# AlteraUSBBlaster2TC.net
KiCad netlist of a schematic drawn in EAGLE
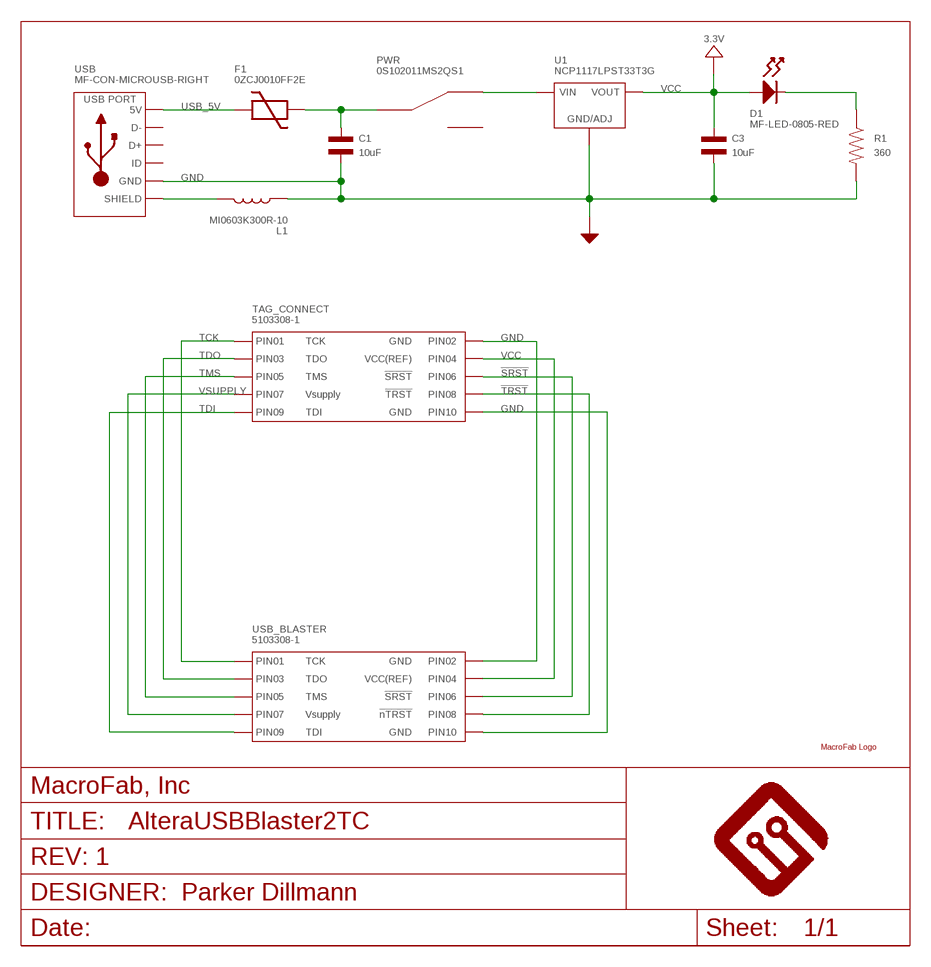
[diagram p0: schematic, sheet 1]

(export (version "E")
  (design (tool "Eeschema 10.0.6"))
  (components
    (comp (ref "C1")
      (value "10uF")
      (footprint "eagle-import:C1206")
      (fields (field (name "MPN") "MF-CAP-1206-10uF"))
      (libsource (lib "eagle-import") (part "CAPACITOR_NP_1206"))
    )
    (comp (ref "C3")
      (value "10uF")
      (footprint "eagle-import:C1206")
      (fields (field (name "MPN") "MF-CAP-1206-10uF"))
      (libsource (lib "eagle-import") (part "CAPACITOR_NP_1206"))
    )
    (comp (ref "D1")
      (value "MF-LED-0805-RED")
      (footprint "eagle-import:LED0805")
      (fields (field (name "HOUSEPART") "YES"))
      (libsource (lib "eagle-import") (part "LED_SINGLE-0805-RED"))
    )
    (comp (ref "F1")
      (value "0ZCJ0010FF2E")
      (footprint "eagle-import:1206")
      (libsource (lib "eagle-import") (part "PTC_FUSE_1206"))
    )
    (comp (ref "FRAME1")
      (value "MF_FRAMEDEFAULT")
      (footprint "eagle-import:MF_FRAME_DEFAULT")
      (fields
        (field (name "HOUSEPART") "0")
        (field (name "DNAME") "Parker Dillmann")
        (field (name "REVNUM") "REV: 1")
      )
      (libsource (lib "eagle-import") (part "MF_FRAMEDEFAULT"))
    )
    (comp (ref "L1")
      (value "MI0603K300R-10")
      (footprint "eagle-import:L0603")
      (fields (field (name "MPN") "MI0603K300R-10"))
      (libsource (lib "eagle-import") (part "INDUCTOR_0603"))
    )
    (comp (ref "PWR")
      (value "0S102011MS2QS1")
      (footprint "eagle-import:0S102011MS2QS1")
      (libsource (lib "eagle-import") (part "SPDT_0S102011MS2QS1"))
    )
    (comp (ref "R1")
      (value "360")
      (footprint "eagle-import:R0805")
      (fields (field (name "MPN") "MF-RES-0805-360"))
      (libsource (lib "eagle-import") (part "RESISTOR_0805"))
    )
    (comp (ref "TAG_CONNECT")
      (value "5103308-1")
      (footprint "eagle-import:5103308-1")
      (fields
        (field (name "LABEL01") "TCK")
        (field (name "LABEL02") "GND")
        (field (name "LABEL03") "TDO")
        (field (name "LABEL04") "VCC(REF)")
        (field (name "LABEL05") "TMS")
        (field (name "LABEL06") "!SRST")
        (field (name "LABEL07") "Vsupply")
        (field (name "LABEL08") "!TRST")
        (field (name "LABEL09") "TDI")
        (field (name "LABEL10") "GND")
        (field (name "MPN") "5103308-1")
        (field (name "POPULATE") "1")
      )
      (libsource (lib "eagle-import") (part "CON_02X05_5103308-1"))
    )
    (comp (ref "U$3")
      (value "MF_LOGOLOGO_MEDIUM")
      (footprint "eagle-import:MF_LOGO_MEDIUM")
      (libsource (lib "eagle-import") (part "MF_LOGOLOGO_MEDIUM"))
    )
    (comp (ref "U1")
      (value "NCP1117LPST33T3G")
      (footprint "eagle-import:SOT-223-3")
      (fields (field (name "HOUSEPART") "NO"))
      (libsource (lib "eagle-import") (part "NCP1117LPST33T3G"))
    )
    (comp (ref "USB")
      (value "MF-CON-MICROUSB-RIGHT")
      (footprint "eagle-import:MICROUSB-RIGHT")
      (fields (field (name "HOUSEPART") "YES"))
      (libsource (lib "eagle-import") (part "USB_MICRO_RIGHT"))
    )
    (comp (ref "USB_BLASTER")
      (value "5103308-1")
      (footprint "eagle-import:5103308-1")
      (fields
        (field (name "LABEL01") "TCK")
        (field (name "LABEL02") "GND")
        (field (name "LABEL03") "TDO")
        (field (name "LABEL04") "VCC(REF)")
        (field (name "LABEL05") "TMS")
        (field (name "LABEL06") "!SRST")
        (field (name "LABEL07") "Vsupply")
        (field (name "LABEL08") "!nTRST")
        (field (name "LABEL09") "TDI")
        (field (name "LABEL10") "GND")
        (field (name "MPN") "5103308-1")
        (field (name "POPULATE") "1")
      )
      (libsource (lib "eagle-import") (part "CON_02X05_5103308-1"))
    )
  )
  (nets
    (net (code "1") (name "/TCK") (class "Default")
      (node (ref "TAG_CONNECT") (pin "1") (pinfunction "PIN1_1") (pintype "bidirectional"))
      (node (ref "USB_BLASTER") (pin "1") (pinfunction "PIN1_1") (pintype "bidirectional"))
    )
    (net (code "2") (name "/TDI") (class "Default")
      (node (ref "TAG_CONNECT") (pin "9") (pinfunction "PIN9_9") (pintype "bidirectional"))
      (node (ref "USB_BLASTER") (pin "9") (pinfunction "PIN9_9") (pintype "bidirectional"))
    )
    (net (code "3") (name "/TDO") (class "Default")
      (node (ref "TAG_CONNECT") (pin "3") (pinfunction "PIN3_3") (pintype "bidirectional"))
      (node (ref "USB_BLASTER") (pin "3") (pinfunction "PIN3_3") (pintype "bidirectional"))
    )
    (net (code "4") (name "/TMS") (class "Default")
      (node (ref "TAG_CONNECT") (pin "5") (pinfunction "PIN5_5") (pintype "bidirectional"))
      (node (ref "USB_BLASTER") (pin "5") (pinfunction "PIN5_5") (pintype "bidirectional"))
    )
    (net (code "5") (name "/USB_5V") (class "Default")
      (node (ref "F1") (pin "1") (pinfunction "P$1_1") (pintype "bidirectional"))
      (node (ref "USB") (pin "1") (pinfunction "5V_1") (pintype "power_in"))
    )
    (net (code "6") (name "/VSUPPLY") (class "Default")
      (node (ref "TAG_CONNECT") (pin "7") (pinfunction "PIN7_7") (pintype "bidirectional"))
      (node (ref "USB_BLASTER") (pin "7") (pinfunction "PIN7_7") (pintype "bidirectional"))
    )
    (net (code "7") (name "/~{SRST}") (class "Default")
      (node (ref "TAG_CONNECT") (pin "6") (pinfunction "PIN6_6") (pintype "bidirectional"))
      (node (ref "USB_BLASTER") (pin "6") (pinfunction "PIN6_6") (pintype "bidirectional"))
    )
    (net (code "8") (name "/~{TRST}") (class "Default")
      (node (ref "TAG_CONNECT") (pin "8") (pinfunction "PIN8_8") (pintype "bidirectional"))
      (node (ref "USB_BLASTER") (pin "8") (pinfunction "PIN8_8") (pintype "bidirectional"))
    )
    (net (code "9") (name "3.3V") (class "Default")
      (node (ref "C3") (pin "P$1") (pinfunction "P$1_P$1") (pintype "passive"))
      (node (ref "D1") (pin "ANODE") (pinfunction "ANODE_ANODE") (pintype "power_in"))
      (node (ref "TAG_CONNECT") (pin "4") (pinfunction "PIN4_4") (pintype "bidirectional"))
      (node (ref "U1") (pin "P$1") (pinfunction "VOUT_P$1") (pintype "bidirectional"))
      (node (ref "U1") (pin "P$3") (pinfunction "VOUT_P$3") (pintype "bidirectional"))
      (node (ref "USB_BLASTER") (pin "4") (pinfunction "PIN4_4") (pintype "bidirectional"))
    )
    (net (code "10") (name "GND_RAIL") (class "Default")
      (node (ref "C1") (pin "P$2") (pinfunction "P$2_P$2") (pintype "passive"))
      (node (ref "C3") (pin "P$2") (pinfunction "P$2_P$2") (pintype "passive"))
      (node (ref "L1") (pin "P$1") (pinfunction "P$1_P$1") (pintype "passive"))
      (node (ref "R1") (pin "P$2") (pinfunction "P$2_P$2") (pintype "passive"))
      (node (ref "TAG_CONNECT") (pin "10") (pinfunction "PIN10_10") (pintype "bidirectional"))
      (node (ref "TAG_CONNECT") (pin "2") (pinfunction "PIN2_2") (pintype "bidirectional"))
      (node (ref "U1") (pin "P$2") (pinfunction "GND/ADJ_P$2") (pintype "bidirectional"))
      (node (ref "USB") (pin "5") (pinfunction "GND_5") (pintype "power_in"))
      (node (ref "USB_BLASTER") (pin "10") (pinfunction "PIN10_10") (pintype "bidirectional"))
      (node (ref "USB_BLASTER") (pin "2") (pinfunction "PIN2_2") (pintype "bidirectional"))
    )
    (net (code "11") (name "Net-(D1-PadCATHODE)") (class "Default")
      (node (ref "D1") (pin "CATHODE") (pinfunction "CATHODE_CATHODE") (pintype "power_in"))
      (node (ref "R1") (pin "P$1") (pinfunction "P$1_P$1") (pintype "passive"))
    )
    (net (code "12") (name "Net-(F1-P$2)") (class "Default")
      (node (ref "C1") (pin "P$1") (pinfunction "P$1_P$1") (pintype "passive"))
      (node (ref "F1") (pin "2") (pinfunction "P$2_2") (pintype "bidirectional"))
      (node (ref "PWR") (pin "2") (pinfunction "C_2") (pintype "bidirectional"))
    )
    (net (code "13") (name "Net-(L1-PadP$2)") (class "Default")
      (node (ref "L1") (pin "P$2") (pinfunction "P$2_P$2") (pintype "passive"))
      (node (ref "USB") (pin "S1") (pinfunction "SLD_S1") (pintype "power_in"))
      (node (ref "USB") (pin "S2") (pinfunction "SLD_S2") (pintype "power_in"))
      (node (ref "USB") (pin "S3") (pinfunction "SLD_S3") (pintype "power_in"))
      (node (ref "USB") (pin "S4") (pinfunction "SLD_S4") (pintype "power_in"))
      (node (ref "USB") (pin "S5") (pinfunction "SLD_S5") (pintype "power_in"))
      (node (ref "USB") (pin "S6") (pinfunction "SLD_S6") (pintype "power_in"))
    )
    (net (code "14") (name "Net-(U1-VIN)") (class "Default")
      (node (ref "PWR") (pin "1") (pinfunction "1_1") (pintype "bidirectional"))
      (node (ref "U1") (pin "P$4") (pinfunction "VIN_P$4") (pintype "bidirectional"))
    )
    (net (code "15") (name "unconnected-(PWR-2-Pad3)") (class "Default")
      (node (ref "PWR") (pin "3") (pinfunction "2_3") (pintype "bidirectional"))
    )
    (net (code "16") (name "unconnected-(USB-D+-Pad3)") (class "Default")
      (node (ref "USB") (pin "3") (pinfunction "D+_3") (pintype "bidirectional"))
    )
    (net (code "17") (name "unconnected-(USB-D--Pad2)") (class "Default")
      (node (ref "USB") (pin "2") (pinfunction "D-_2") (pintype "bidirectional"))
    )
    (net (code "18") (name "unconnected-(USB-ID-Pad4)") (class "Default")
      (node (ref "USB") (pin "4") (pinfunction "ID_4") (pintype "bidirectional"))
    )
  )
)
